# boardV3.net
KiCad netlist of a schematic drawn in EAGLE
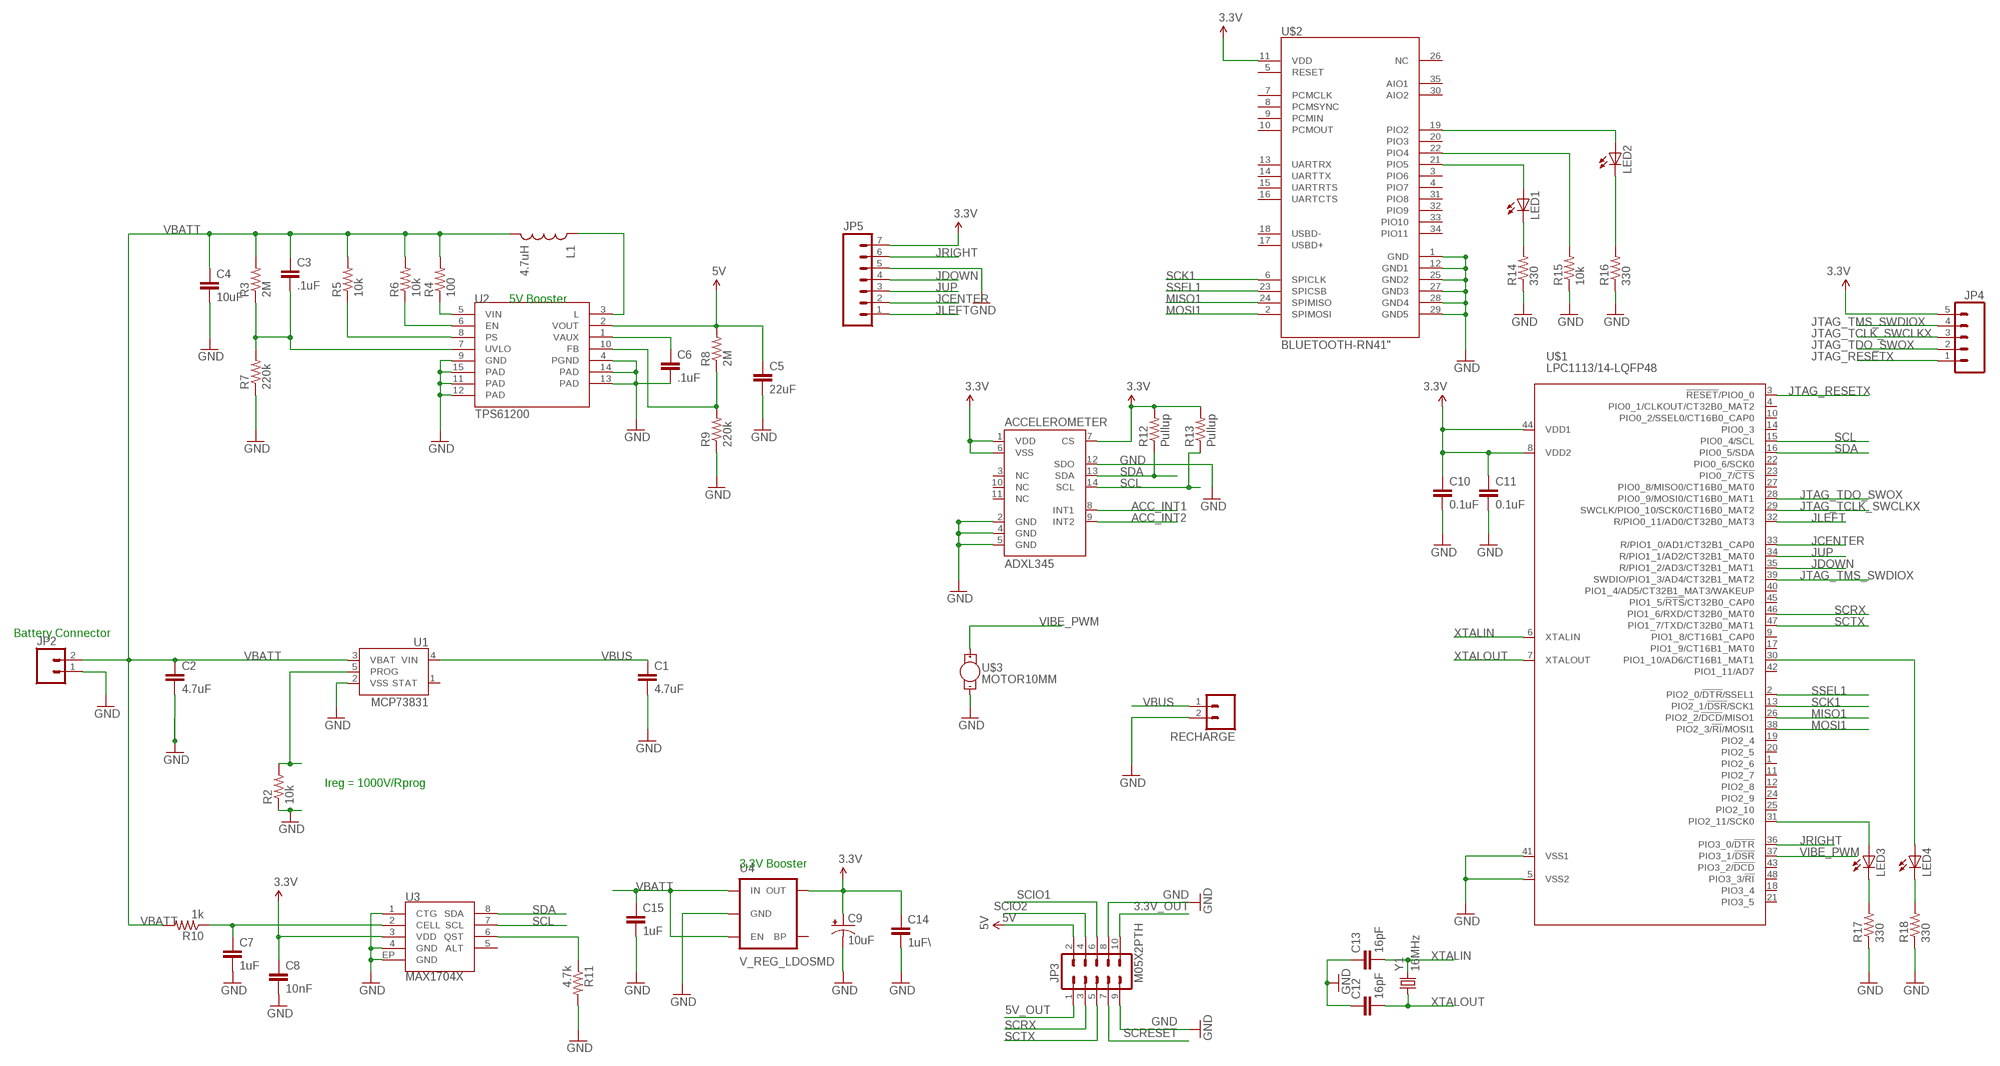
[diagram p0: schematic, sheet 1, part 1 of 2]
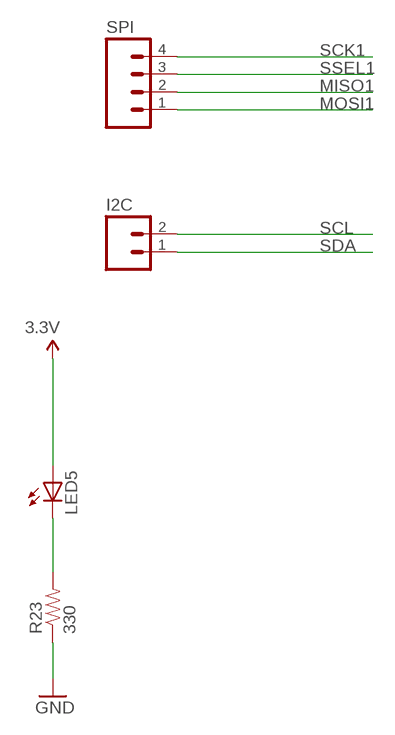
[diagram p1: schematic, sheet 1, part 2 of 2]
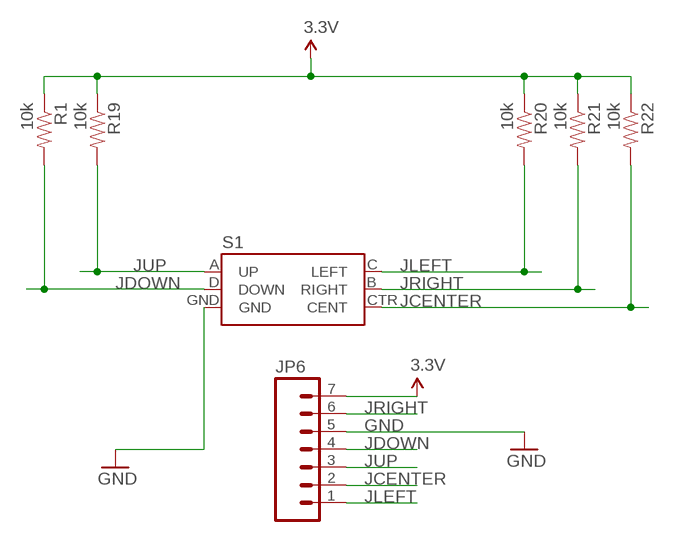
[diagram p2: schematic, sheet 2]

(export (version "E")
  (design (tool "Eeschema 10.0.6"))
  (components
    (comp (ref "ACCELEROMETER")
      (value "ADXL345")
      (footprint "eagle-import:LGA14")
      (libsource (lib "eagle-import") (part "ADXL345"))
    )
    (comp (ref "C1")
      (value "4.7uF")
      (footprint "eagle-import:0603-CAP")
      (libsource (lib "eagle-import") (part "CAP0603-CAP"))
    )
    (comp (ref "C2")
      (value "4.7uF")
      (footprint "eagle-import:0603-CAP")
      (libsource (lib "eagle-import") (part "CAP0603-CAP"))
    )
    (comp (ref "C3")
      (value ".1uF")
      (footprint "eagle-import:0603-CAP")
      (libsource (lib "eagle-import") (part "CAP0603-CAP"))
    )
    (comp (ref "C4")
      (value "10uF")
      (footprint "eagle-import:0603-CAP")
      (libsource (lib "eagle-import") (part "CAP0603-CAP"))
    )
    (comp (ref "C5")
      (value "22uF")
      (footprint "eagle-import:0603-CAP")
      (libsource (lib "eagle-import") (part "CAP0603-CAP"))
    )
    (comp (ref "C6")
      (value ".1uF")
      (footprint "eagle-import:0603-CAP")
      (libsource (lib "eagle-import") (part "CAP0603-CAP"))
    )
    (comp (ref "C7")
      (value "1uF")
      (footprint "eagle-import:0603-CAP")
      (libsource (lib "eagle-import") (part "CAP0603-CAP"))
    )
    (comp (ref "C8")
      (value "10nF")
      (footprint "eagle-import:0603-CAP")
      (libsource (lib "eagle-import") (part "CAP0603-CAP"))
    )
    (comp (ref "C9")
      (value "10uF")
      (footprint "eagle-import:EIA3216")
      (libsource (lib "eagle-import") (part "10UF-TANT"))
    )
    (comp (ref "C10")
      (value "0.1uF")
      (footprint "eagle-import:0603-CAP")
      (libsource (lib "eagle-import") (part "CAP0603-CAP"))
    )
    (comp (ref "C11")
      (value "0.1uF")
      (footprint "eagle-import:0603-CAP")
      (libsource (lib "eagle-import") (part "CAP0603-CAP"))
    )
    (comp (ref "C12")
      (value "16pF")
      (footprint "eagle-import:0603-CAP")
      (libsource (lib "eagle-import") (part "CAP0603-CAP"))
    )
    (comp (ref "C13")
      (value "16pF")
      (footprint "eagle-import:0603-CAP")
      (libsource (lib "eagle-import") (part "CAP0603-CAP"))
    )
    (comp (ref "C14")
      (value "1uF\\")
      (footprint "eagle-import:0603-CAP")
      (libsource (lib "eagle-import") (part "CAP0603-CAP"))
    )
    (comp (ref "C15")
      (value "1uF")
      (footprint "eagle-import:0603-CAP")
      (libsource (lib "eagle-import") (part "CAP0603-CAP"))
    )
    (comp (ref "I2C")
      (value "M02POLAR")
      (footprint "eagle-import:MOLEX-1X2")
      (libsource (lib "eagle-import") (part "M02POLAR"))
    )
    (comp (ref "JP2")
      (value "M02PTH")
      (footprint "eagle-import:1X02")
      (libsource (lib "eagle-import") (part "M02PTH"))
    )
    (comp (ref "JP3")
      (value "M05X2PTH")
      (footprint "eagle-import:AVR_ICSP")
      (libsource (lib "eagle-import") (part "M05X2PTH"))
    )
    (comp (ref "JP4")
      (value "M05PTH")
      (footprint "eagle-import:1X05")
      (libsource (lib "eagle-import") (part "M05PTH"))
    )
    (comp (ref "JP5")
      (value "M07")
      (footprint "eagle-import:1X07")
      (libsource (lib "eagle-import") (part "M07"))
    )
    (comp (ref "L1")
      (value "4.7uH")
      (footprint "eagle-import:CDRH2D09")
      (libsource (lib "eagle-import") (part "INDUCTOR."))
    )
    (comp (ref "LED1")
      (value "LED0603")
      (footprint "eagle-import:LED-0603")
      (libsource (lib "eagle-import") (part "LED0603"))
    )
    (comp (ref "LED2")
      (value "LED0603")
      (footprint "eagle-import:LED-0603")
      (libsource (lib "eagle-import") (part "LED0603"))
    )
    (comp (ref "LED3")
      (value "LED0603")
      (footprint "eagle-import:LED-0603")
      (libsource (lib "eagle-import") (part "LED0603"))
    )
    (comp (ref "LED4")
      (value "LED0603")
      (footprint "eagle-import:LED-0603")
      (libsource (lib "eagle-import") (part "LED0603"))
    )
    (comp (ref "LED5")
      (value "LED0603")
      (footprint "eagle-import:LED-0603")
      (libsource (lib "eagle-import") (part "LED0603"))
    )
    (comp (ref "R2")
      (value "10k")
      (footprint "eagle-import:0603-RES")
      (libsource (lib "eagle-import") (part "RESISTOR0603-RES"))
    )
    (comp (ref "R3")
      (value "2M")
      (footprint "eagle-import:0603-RES")
      (libsource (lib "eagle-import") (part "RESISTOR0603-RES"))
    )
    (comp (ref "R4")
      (value "100")
      (footprint "eagle-import:0603-RES")
      (libsource (lib "eagle-import") (part "RESISTOR0603-RES"))
    )
    (comp (ref "R5")
      (value "10k")
      (footprint "eagle-import:0603-RES")
      (libsource (lib "eagle-import") (part "RESISTOR0603-RES"))
    )
    (comp (ref "R6")
      (value "10k")
      (footprint "eagle-import:0603-RES")
      (libsource (lib "eagle-import") (part "RESISTOR0603-RES"))
    )
    (comp (ref "R7")
      (value "220k")
      (footprint "eagle-import:0603-RES")
      (libsource (lib "eagle-import") (part "RESISTOR0603-RES"))
    )
    (comp (ref "R8")
      (value "2M")
      (footprint "eagle-import:0603-RES")
      (libsource (lib "eagle-import") (part "SparkFun-Resistors_RESISTOR0603-RES"))
    )
    (comp (ref "R9")
      (value "220k")
      (footprint "eagle-import:0603-RES")
      (libsource (lib "eagle-import") (part "SparkFun-Resistors_RESISTOR0603-RES"))
    )
    (comp (ref "R10")
      (value "1k")
      (footprint "eagle-import:0603-RES")
      (libsource (lib "eagle-import") (part "RESISTOR0603-RES"))
    )
    (comp (ref "R11")
      (value "4.7k")
      (footprint "eagle-import:0603-RES")
      (libsource (lib "eagle-import") (part "RESISTOR0603-RES"))
    )
    (comp (ref "R12")
      (value "Pullup")
      (footprint "eagle-import:0603-RES")
      (libsource (lib "eagle-import") (part "SparkFun-Resistors_RESISTOR0603-RES"))
    )
    (comp (ref "R13")
      (value "Pullup")
      (footprint "eagle-import:0603-RES")
      (libsource (lib "eagle-import") (part "SparkFun-Resistors_RESISTOR0603-RES"))
    )
    (comp (ref "R14")
      (value "330")
      (footprint "eagle-import:0603-RES")
      (libsource (lib "eagle-import") (part "RESISTOR0603-RES"))
    )
    (comp (ref "R15")
      (value "10k")
      (footprint "eagle-import:0603-RES")
      (libsource (lib "eagle-import") (part "RESISTOR0603-RES"))
    )
    (comp (ref "R16")
      (value "330")
      (footprint "eagle-import:0603-RES")
      (libsource (lib "eagle-import") (part "RESISTOR0603-RES"))
    )
    (comp (ref "R17")
      (value "330")
      (footprint "eagle-import:0603-RES")
      (libsource (lib "eagle-import") (part "RESISTOR0603-RES"))
    )
    (comp (ref "R18")
      (value "330")
      (footprint "eagle-import:0603-RES")
      (libsource (lib "eagle-import") (part "RESISTOR0603-RES"))
    )
    (comp (ref "R23")
      (value "330")
      (footprint "eagle-import:0603-RES")
      (libsource (lib "eagle-import") (part "RESISTOR0603-RES"))
    )
    (comp (ref "RECHARGE")
      (value "M02POLAR")
      (footprint "eagle-import:MOLEX-1X2")
      (libsource (lib "eagle-import") (part "M02POLAR"))
    )
    (comp (ref "SPI")
      (value "M04POLAR")
      (footprint "eagle-import:MOLEX-1X4")
      (libsource (lib "eagle-import") (part "M04POLAR"))
    )
    (comp (ref "U$1")
      (value "LPC1113/14-LQFP48")
      (footprint "eagle-import:LQFP48")
      (libsource (lib "eagle-import") (part "LPC1113/14-LQFP48"))
    )
    (comp (ref "U$2")
      (value "BLUETOOTH-RN41\"")
      (footprint "eagle-import:RN41")
      (libsource (lib "eagle-import") (part "BLUETOOTH-RN41{dblquote}"))
    )
    (comp (ref "U$3")
      (value "MOTOR10MM")
      (footprint "eagle-import:VIBE-MOTOR-10MM")
      (libsource (lib "eagle-import") (part "MOTOR10MM"))
    )
    (comp (ref "U1")
      (value "MCP73831")
      (footprint "eagle-import:SOT23-5")
      (libsource (lib "eagle-import") (part "MCP73831"))
    )
    (comp (ref "U2")
      (value "TPS61200")
      (footprint "eagle-import:QFN-10_PAD")
      (libsource (lib "eagle-import") (part "TPS61200"))
    )
    (comp (ref "U3")
      (value "MAX1704X")
      (footprint "eagle-import:TDFN-8")
      (libsource (lib "eagle-import") (part "MAX1704X"))
    )
    (comp (ref "U4")
      (value "V_REG_LDOSMD")
      (footprint "eagle-import:SOT23-5")
      (libsource (lib "eagle-import") (part "V_REG_LDOSMD"))
    )
    (comp (ref "Y1")
      (value "16MHz")
      (footprint "eagle-import:CRYSTAL-SMD-5X3")
      (libsource (lib "eagle-import") (part "CRYSTAL5X3"))
    )
    (comp (ref "JP6")
      (value "M07")
      (footprint "eagle-import:1X07")
      (libsource (lib "eagle-import") (part "M07"))
    )
    (comp (ref "R1")
      (value "10k")
      (footprint "eagle-import:0603-RES")
      (libsource (lib "eagle-import") (part "SparkFun-Resistors_RESISTOR0603-RES"))
    )
    (comp (ref "R19")
      (value "10k")
      (footprint "eagle-import:0603-RES")
      (libsource (lib "eagle-import") (part "SparkFun-Resistors_RESISTOR0603-RES"))
    )
    (comp (ref "R20")
      (value "10k")
      (footprint "eagle-import:0603-RES")
      (libsource (lib "eagle-import") (part "SparkFun-Resistors_RESISTOR0603-RES"))
    )
    (comp (ref "R21")
      (value "10k")
      (footprint "eagle-import:0603-RES")
      (libsource (lib "eagle-import") (part "SparkFun-Resistors_RESISTOR0603-RES"))
    )
    (comp (ref "R22")
      (value "10k")
      (footprint "eagle-import:0603-RES")
      (libsource (lib "eagle-import") (part "SparkFun-Resistors_RESISTOR0603-RES"))
    )
    (comp (ref "S1")
      (value "JOYSTICK_MINI")
      (footprint "eagle-import:JOYSTICK_MINI")
      (libsource (lib "eagle-import") (part "JOYSTICK_MINI"))
    )
  )
  (nets
    (net (code "1") (name "3.3V") (class "Default")
      (node (ref "ACCELEROMETER") (pin "1") (pinfunction "VDD_1") (pintype "bidirectional"))
      (node (ref "ACCELEROMETER") (pin "6") (pinfunction "VSS_6") (pintype "bidirectional"))
      (node (ref "ACCELEROMETER") (pin "7") (pinfunction "CS_7") (pintype "bidirectional"))
      (node (ref "C10") (pin "1") (pinfunction "1_1") (pintype "passive"))
      (node (ref "C11") (pin "1") (pinfunction "1_1") (pintype "passive"))
      (node (ref "C14") (pin "1") (pinfunction "1_1") (pintype "passive"))
      (node (ref "C8") (pin "1") (pinfunction "1_1") (pintype "passive"))
      (node (ref "C9") (pin "A") (pinfunction "+_A") (pintype "passive"))
      (node (ref "JP4") (pin "5") (pinfunction "5_5") (pintype "passive"))
      (node (ref "JP5") (pin "7") (pinfunction "7_7") (pintype "passive"))
      (node (ref "JP6") (pin "7") (pinfunction "7_7") (pintype "passive"))
      (node (ref "LED5") (pin "A") (pinfunction "A_A") (pintype "passive"))
      (node (ref "R1") (pin "1") (pinfunction "1_1") (pintype "passive"))
      (node (ref "R12") (pin "2") (pinfunction "2_2") (pintype "passive"))
      (node (ref "R13") (pin "2") (pinfunction "2_2") (pintype "passive"))
      (node (ref "R19") (pin "1") (pinfunction "1_1") (pintype "passive"))
      (node (ref "R20") (pin "1") (pinfunction "1_1") (pintype "passive"))
      (node (ref "R21") (pin "1") (pinfunction "1_1") (pintype "passive"))
      (node (ref "R22") (pin "1") (pinfunction "1_1") (pintype "passive"))
      (node (ref "U$1") (pin "44") (pinfunction "VDD1_44") (pintype "power_in"))
      (node (ref "U$1") (pin "8") (pinfunction "VDD2_8") (pintype "power_in"))
      (node (ref "U$2") (pin "11") (pinfunction "VDD_11") (pintype "bidirectional"))
      (node (ref "U3") (pin "3") (pinfunction "VDD_3") (pintype "bidirectional"))
      (node (ref "U4") (pin "5") (pinfunction "OUT_5") (pintype "passive"))
    )
    (net (code "2") (name "3.3V_OUT") (class "Default")
      (node (ref "JP3") (pin "10") (pinfunction "10_10") (pintype "passive"))
    )
    (net (code "3") (name "5V") (class "Default")
      (node (ref "C5") (pin "1") (pinfunction "1_1") (pintype "passive"))
      (node (ref "JP3") (pin "2") (pinfunction "2_2") (pintype "passive"))
      (node (ref "R8") (pin "2") (pinfunction "2_2") (pintype "passive"))
      (node (ref "U2") (pin "2") (pinfunction "VOUT_2") (pintype "passive"))
    )
    (net (code "4") (name "5V_OUT") (class "Default")
      (node (ref "JP3") (pin "1") (pinfunction "1_1") (pintype "passive"))
    )
    (net (code "5") (name "ACC_INT1") (class "Default")
      (node (ref "ACCELEROMETER") (pin "8") (pinfunction "INT1_8") (pintype "bidirectional"))
    )
    (net (code "6") (name "ACC_INT2") (class "Default")
      (node (ref "ACCELEROMETER") (pin "9") (pinfunction "INT2_9") (pintype "bidirectional"))
    )
    (net (code "7") (name "GND") (class "Default")
      (node (ref "ACCELEROMETER") (pin "12") (pinfunction "SDO_12") (pintype "bidirectional"))
      (node (ref "ACCELEROMETER") (pin "2") (pinfunction "GND_2") (pintype "bidirectional"))
      (node (ref "ACCELEROMETER") (pin "4") (pinfunction "GND_4") (pintype "bidirectional"))
      (node (ref "ACCELEROMETER") (pin "5") (pinfunction "GND_5") (pintype "bidirectional"))
      (node (ref "C1") (pin "2") (pinfunction "2_2") (pintype "passive"))
      (node (ref "C10") (pin "2") (pinfunction "2_2") (pintype "passive"))
      (node (ref "C11") (pin "2") (pinfunction "2_2") (pintype "passive"))
      (node (ref "C12") (pin "1") (pinfunction "1_1") (pintype "passive"))
      (node (ref "C13") (pin "1") (pinfunction "1_1") (pintype "passive"))
      (node (ref "C14") (pin "2") (pinfunction "2_2") (pintype "passive"))
      (node (ref "C15") (pin "2") (pinfunction "2_2") (pintype "passive"))
      (node (ref "C2") (pin "2") (pinfunction "2_2") (pintype "passive"))
      (node (ref "C4") (pin "2") (pinfunction "2_2") (pintype "passive"))
      (node (ref "C5") (pin "2") (pinfunction "2_2") (pintype "passive"))
      (node (ref "C6") (pin "2") (pinfunction "2_2") (pintype "passive"))
      (node (ref "C7") (pin "2") (pinfunction "2_2") (pintype "passive"))
      (node (ref "C8") (pin "2") (pinfunction "2_2") (pintype "passive"))
      (node (ref "C9") (pin "C") (pinfunction "-_C") (pintype "passive"))
      (node (ref "JP2") (pin "1") (pinfunction "1_1") (pintype "passive"))
      (node (ref "JP3") (pin "8") (pinfunction "8_8") (pintype "passive"))
      (node (ref "JP3") (pin "9") (pinfunction "9_9") (pintype "passive"))
      (node (ref "JP5") (pin "5") (pinfunction "5_5") (pintype "passive"))
      (node (ref "JP6") (pin "5") (pinfunction "5_5") (pintype "passive"))
      (node (ref "R11") (pin "2") (pinfunction "2_2") (pintype "passive"))
      (node (ref "R14") (pin "1") (pinfunction "1_1") (pintype "passive"))
      (node (ref "R15") (pin "1") (pinfunction "1_1") (pintype "passive"))
      (node (ref "R16") (pin "1") (pinfunction "1_1") (pintype "passive"))
      (node (ref "R17") (pin "1") (pinfunction "1_1") (pintype "passive"))
      (node (ref "R18") (pin "1") (pinfunction "1_1") (pintype "passive"))
      (node (ref "R2") (pin "1") (pinfunction "1_1") (pintype "passive"))
      (node (ref "R23") (pin "1") (pinfunction "1_1") (pintype "passive"))
      (node (ref "R7") (pin "1") (pinfunction "1_1") (pintype "passive"))
      (node (ref "R9") (pin "1") (pinfunction "1_1") (pintype "passive"))
      (node (ref "RECHARGE") (pin "2") (pinfunction "2_2") (pintype "passive"))
      (node (ref "S1") (pin "GND") (pinfunction "GND_GND") (pintype "bidirectional"))
      (node (ref "U$1") (pin "41") (pinfunction "VSS1_41") (pintype "power_in"))
      (node (ref "U$1") (pin "5") (pinfunction "VSS2_5") (pintype "power_in"))
      (node (ref "U$2") (pin "1") (pinfunction "GND_1") (pintype "bidirectional"))
      (node (ref "U$2") (pin "12") (pinfunction "GND1_12") (pintype "bidirectional"))
      (node (ref "U$2") (pin "25") (pinfunction "GND2_25") (pintype "bidirectional"))
      (node (ref "U$2") (pin "27") (pinfunction "GND3_27") (pintype "bidirectional"))
      (node (ref "U$2") (pin "28") (pinfunction "GND4_28") (pintype "bidirectional"))
      (node (ref "U$2") (pin "29") (pinfunction "GND5_29") (pintype "bidirectional"))
      (node (ref "U$3") (pin "-") (pinfunction "-_-") (pintype "bidirectional"))
      (node (ref "U1") (pin "2") (pinfunction "VSS_2") (pintype "power_in"))
      (node (ref "U2") (pin "11") (pinfunction "PAD_11") (pintype "power_in"))
      (node (ref "U2") (pin "12") (pinfunction "PAD_12") (pintype "power_in"))
      (node (ref "U2") (pin "13") (pinfunction "PAD_13") (pintype "power_in"))
      (node (ref "U2") (pin "14") (pinfunction "PAD_14") (pintype "power_in"))
      (node (ref "U2") (pin "15") (pinfunction "PAD_15") (pintype "power_in"))
      (node (ref "U2") (pin "4") (pinfunction "PGND_4") (pintype "power_in"))
      (node (ref "U2") (pin "9") (pinfunction "GND_9") (pintype "power_in"))
      (node (ref "U3") (pin "1") (pinfunction "CTG_1") (pintype "bidirectional"))
      (node (ref "U3") (pin "4") (pinfunction "GND_4") (pintype "bidirectional"))
      (node (ref "U3") (pin "EP") (pinfunction "GND_EP") (pintype "bidirectional"))
      (node (ref "U4") (pin "2") (pinfunction "GND_2") (pintype "input"))
    )
    (net (code "8") (name "JCENTER") (class "Default")
      (node (ref "JP5") (pin "2") (pinfunction "2_2") (pintype "passive"))
      (node (ref "JP6") (pin "2") (pinfunction "2_2") (pintype "passive"))
      (node (ref "R22") (pin "2") (pinfunction "2_2") (pintype "passive"))
      (node (ref "S1") (pin "CTR") (pinfunction "CENT_CTR") (pintype "bidirectional"))
      (node (ref "U$1") (pin "33") (pinfunction "R/PIO1_0/AD1/CT32B1_CAP0_33") (pintype "bidirectional"))
    )
    (net (code "9") (name "JDOWN") (class "Default")
      (node (ref "JP5") (pin "4") (pinfunction "4_4") (pintype "passive"))
      (node (ref "JP6") (pin "4") (pinfunction "4_4") (pintype "passive"))
      (node (ref "R1") (pin "2") (pinfunction "2_2") (pintype "passive"))
      (node (ref "S1") (pin "D") (pinfunction "DOWN_D") (pintype "bidirectional"))
      (node (ref "U$1") (pin "35") (pinfunction "R/PIO1_2/AD3/CT32B1_MAT1_35") (pintype "bidirectional"))
    )
    (net (code "10") (name "JLEFT") (class "Default")
      (node (ref "JP5") (pin "1") (pinfunction "1_1") (pintype "passive"))
      (node (ref "JP6") (pin "1") (pinfunction "1_1") (pintype "passive"))
      (node (ref "R20") (pin "2") (pinfunction "2_2") (pintype "passive"))
      (node (ref "S1") (pin "C") (pinfunction "LEFT_C") (pintype "bidirectional"))
      (node (ref "U$1") (pin "32") (pinfunction "R/PIO0_11/AD0/CT32B0_MAT3_32") (pintype "bidirectional"))
    )
    (net (code "11") (name "JRIGHT") (class "Default")
      (node (ref "JP5") (pin "6") (pinfunction "6_6") (pintype "passive"))
      (node (ref "JP6") (pin "6") (pinfunction "6_6") (pintype "passive"))
      (node (ref "R21") (pin "2") (pinfunction "2_2") (pintype "passive"))
      (node (ref "S1") (pin "B") (pinfunction "RIGHT_B") (pintype "bidirectional"))
      (node (ref "U$1") (pin "36") (pinfunction "PIO3_0/~{DTR}_36") (pintype "bidirectional"))
    )
    (net (code "12") (name "JTAG_RESETX") (class "Default")
      (node (ref "JP4") (pin "1") (pinfunction "1_1") (pintype "passive"))
      (node (ref "U$1") (pin "3") (pinfunction "~{RESET}/PIO0_0_3") (pintype "bidirectional"))
    )
    (net (code "13") (name "JTAG_TCLK_SWCLKX") (class "Default")
      (node (ref "JP4") (pin "3") (pinfunction "3_3") (pintype "passive"))
      (node (ref "U$1") (pin "29") (pinfunction "SWCLK/PIO0_10/SCK0/CT16B0_MAT2_29") (pintype "bidirectional"))
    )
    (net (code "14") (name "JTAG_TDO_SWOX") (class "Default")
      (node (ref "JP4") (pin "2") (pinfunction "2_2") (pintype "passive"))
      (node (ref "U$1") (pin "28") (pinfunction "PIO0_9/MOSI0/CT16B0_MAT1_28") (pintype "bidirectional"))
    )
    (net (code "15") (name "JTAG_TMS_SWDIOX") (class "Default")
      (node (ref "JP4") (pin "4") (pinfunction "4_4") (pintype "passive"))
      (node (ref "U$1") (pin "39") (pinfunction "SWDIO/PIO1_3/AD4/CT32B1_MAT2_39") (pintype "bidirectional"))
    )
    (net (code "16") (name "JUP") (class "Default")
      (node (ref "JP5") (pin "3") (pinfunction "3_3") (pintype "passive"))
      (node (ref "JP6") (pin "3") (pinfunction "3_3") (pintype "passive"))
      (node (ref "R19") (pin "2") (pinfunction "2_2") (pintype "passive"))
      (node (ref "S1") (pin "A") (pinfunction "UP_A") (pintype "bidirectional"))
      (node (ref "U$1") (pin "34") (pinfunction "R/PIO1_1/AD2/CT32B1_MAT0_34") (pintype "bidirectional"))
    )
    (net (code "17") (name "MISO1") (class "Default")
      (node (ref "SPI") (pin "2") (pinfunction "2_2") (pintype "passive"))
      (node (ref "U$1") (pin "26") (pinfunction "PIO2_2/~{DCD}/MISO1_26") (pintype "bidirectional"))
      (node (ref "U$2") (pin "24") (pinfunction "SPIMISO_24") (pintype "bidirectional"))
    )
    (net (code "18") (name "MOSI1") (class "Default")
      (node (ref "SPI") (pin "1") (pinfunction "1_1") (pintype "passive"))
      (node (ref "U$1") (pin "38") (pinfunction "PIO2_3/~{RI}/MOSI1_38") (pintype "bidirectional"))
      (node (ref "U$2") (pin "2") (pinfunction "SPIMOSI_2") (pintype "bidirectional"))
    )
    (net (code "19") (name "Net-(L1-1)") (class "Default")
      (node (ref "L1") (pin "P$1") (pinfunction "1_P$1") (pintype "passive"))
      (node (ref "U2") (pin "3") (pinfunction "L_3") (pintype "passive"))
    )
    (net (code "20") (name "Net-(LED1-PadC)") (class "Default")
      (node (ref "LED1") (pin "C") (pinfunction "C_C") (pintype "passive"))
      (node (ref "R14") (pin "2") (pinfunction "2_2") (pintype "passive"))
    )
    (net (code "21") (name "Net-(LED2-PadC)") (class "Default")
      (node (ref "LED2") (pin "C") (pinfunction "C_C") (pintype "passive"))
      (node (ref "R16") (pin "2") (pinfunction "2_2") (pintype "passive"))
    )
    (net (code "22") (name "Net-(LED3-PadC)") (class "Default")
      (node (ref "LED3") (pin "C") (pinfunction "C_C") (pintype "passive"))
      (node (ref "R17") (pin "2") (pinfunction "2_2") (pintype "passive"))
    )
    (net (code "23") (name "Net-(LED4-PadC)") (class "Default")
      (node (ref "LED4") (pin "C") (pinfunction "C_C") (pintype "passive"))
      (node (ref "R18") (pin "2") (pinfunction "2_2") (pintype "passive"))
    )
    (net (code "24") (name "Net-(LED5-PadC)") (class "Default")
      (node (ref "LED5") (pin "C") (pinfunction "C_C") (pintype "passive"))
      (node (ref "R23") (pin "2") (pinfunction "2_2") (pintype "passive"))
    )
    (net (code "25") (name "Net-(U$1-PIO1_10{slash}AD6{slash}CT16B1_MAT1)") (class "Default")
      (node (ref "LED4") (pin "A") (pinfunction "A_A") (pintype "passive"))
      (node (ref "U$1") (pin "30") (pinfunction "PIO1_10/AD6/CT16B1_MAT1_30") (pintype "bidirectional"))
    )
    (net (code "26") (name "Net-(U$1-PIO2_11{slash}SCK0)") (class "Default")
      (node (ref "LED3") (pin "A") (pinfunction "A_A") (pintype "passive"))
      (node (ref "U$1") (pin "31") (pinfunction "PIO2_11/SCK0_31") (pintype "bidirectional"))
    )
    (net (code "27") (name "Net-(U$2-PIO2)") (class "Default")
      (node (ref "LED2") (pin "A") (pinfunction "A_A") (pintype "passive"))
      (node (ref "U$2") (pin "19") (pinfunction "PIO2_19") (pintype "bidirectional"))
    )
    (net (code "28") (name "Net-(U$2-PIO4)") (class "Default")
      (node (ref "R15") (pin "2") (pinfunction "2_2") (pintype "passive"))
      (node (ref "U$2") (pin "22") (pinfunction "PIO4_22") (pintype "bidirectional"))
    )
    (net (code "29") (name "Net-(U$2-PIO5)") (class "Default")
      (node (ref "LED1") (pin "A") (pinfunction "A_A") (pintype "passive"))
      (node (ref "U$2") (pin "21") (pinfunction "PIO5_21") (pintype "bidirectional"))
    )
    (net (code "30") (name "Net-(U1-PROG)") (class "Default")
      (node (ref "R2") (pin "2") (pinfunction "2_2") (pintype "passive"))
      (node (ref "U1") (pin "5") (pinfunction "PROG_5") (pintype "input"))
    )
    (net (code "31") (name "Net-(U2-EN)") (class "Default")
      (node (ref "R6") (pin "1") (pinfunction "1_1") (pintype "passive"))
      (node (ref "U2") (pin "6") (pinfunction "EN_6") (pintype "input"))
    )
    (net (code "32") (name "Net-(U2-FB)") (class "Default")
      (node (ref "R8") (pin "1") (pinfunction "1_1") (pintype "passive"))
      (node (ref "R9") (pin "2") (pinfunction "2_2") (pintype "passive"))
      (node (ref "U2") (pin "10") (pinfunction "FB_10") (pintype "passive"))
    )
    (net (code "33") (name "Net-(U2-PS)") (class "Default")
      (node (ref "R5") (pin "1") (pinfunction "1_1") (pintype "passive"))
      (node (ref "U2") (pin "8") (pinfunction "PS_8") (pintype "input"))
    )
    (net (code "34") (name "Net-(U2-UVLO)") (class "Default")
      (node (ref "C3") (pin "2") (pinfunction "2_2") (pintype "passive"))
      (node (ref "R3") (pin "1") (pinfunction "1_1") (pintype "passive"))
      (node (ref "R7") (pin "2") (pinfunction "2_2") (pintype "passive"))
      (node (ref "U2") (pin "7") (pinfunction "UVLO_7") (pintype "passive"))
    )
    (net (code "35") (name "Net-(U2-VAUX)") (class "Default")
      (node (ref "C6") (pin "1") (pinfunction "1_1") (pintype "passive"))
      (node (ref "U2") (pin "1") (pinfunction "VAUX_1") (pintype "passive"))
    )
    (net (code "36") (name "Net-(U2-VIN)") (class "Default")
      (node (ref "R4") (pin "1") (pinfunction "1_1") (pintype "passive"))
      (node (ref "U2") (pin "5") (pinfunction "VIN_5") (pintype "power_in"))
    )
    (net (code "37") (name "Net-(U3-CELL)") (class "Default")
      (node (ref "C7") (pin "1") (pinfunction "1_1") (pintype "passive"))
      (node (ref "R10") (pin "1") (pinfunction "1_1") (pintype "passive"))
      (node (ref "U3") (pin "2") (pinfunction "CELL_2") (pintype "bidirectional"))
    )
    (net (code "38") (name "Net-(U3-QST)") (class "Default")
      (node (ref "R11") (pin "1") (pinfunction "1_1") (pintype "passive"))
      (node (ref "U3") (pin "6") (pinfunction "QST_6") (pintype "bidirectional"))
    )
    (net (code "39") (name "SCIO1") (class "Default")
      (node (ref "JP3") (pin "6") (pinfunction "6_6") (pintype "passive"))
    )
    (net (code "40") (name "SCIO2") (class "Default")
      (node (ref "JP3") (pin "4") (pinfunction "4_4") (pintype "passive"))
    )
    (net (code "41") (name "SCK1") (class "Default")
      (node (ref "SPI") (pin "4") (pinfunction "4_4") (pintype "passive"))
      (node (ref "U$1") (pin "13") (pinfunction "PIO2_1/~{DSR}/SCK1_13") (pintype "bidirectional"))
      (node (ref "U$2") (pin "6") (pinfunction "SPICLK_6") (pintype "bidirectional"))
    )
    (net (code "42") (name "SCL") (class "Default")
      (node (ref "ACCELEROMETER") (pin "14") (pinfunction "SCL_14") (pintype "bidirectional"))
      (node (ref "I2C") (pin "2") (pinfunction "2_2") (pintype "passive"))
      (node (ref "R13") (pin "1") (pinfunction "1_1") (pintype "passive"))
      (node (ref "U$1") (pin "15") (pinfunction "PIO0_4/SCL_15") (pintype "bidirectional"))
      (node (ref "U3") (pin "7") (pinfunction "SCL_7") (pintype "bidirectional"))
    )
    (net (code "43") (name "SCRESET") (class "Default")
      (node (ref "JP3") (pin "7") (pinfunction "7_7") (pintype "passive"))
    )
    (net (code "44") (name "SCRX") (class "Default")
      (node (ref "JP3") (pin "3") (pinfunction "3_3") (pintype "passive"))
      (node (ref "U$1") (pin "46") (pinfunction "PIO1_6/RXD/CT32B0_MAT0_46") (pintype "bidirectional"))
    )
    (net (code "45") (name "SCTX") (class "Default")
      (node (ref "JP3") (pin "5") (pinfunction "5_5") (pintype "passive"))
      (node (ref "U$1") (pin "47") (pinfunction "PIO1_7/TXD/CT32B0_MAT1_47") (pintype "bidirectional"))
    )
    (net (code "46") (name "SDA") (class "Default")
      (node (ref "ACCELEROMETER") (pin "13") (pinfunction "SDA_13") (pintype "bidirectional"))
      (node (ref "I2C") (pin "1") (pinfunction "1_1") (pintype "passive"))
      (node (ref "R12") (pin "1") (pinfunction "1_1") (pintype "passive"))
      (node (ref "U$1") (pin "16") (pinfunction "PIO0_5/SDA_16") (pintype "bidirectional"))
      (node (ref "U3") (pin "8") (pinfunction "SDA_8") (pintype "bidirectional"))
    )
    (net (code "47") (name "SSEL1") (class "Default")
      (node (ref "SPI") (pin "3") (pinfunction "3_3") (pintype "passive"))
      (node (ref "U$1") (pin "2") (pinfunction "PIO2_0/~{DTR}/SSEL1_2") (pintype "bidirectional"))
      (node (ref "U$2") (pin "23") (pinfunction "SPICSB_23") (pintype "bidirectional"))
    )
    (net (code "48") (name "VBATT") (class "Default")
      (node (ref "C15") (pin "1") (pinfunction "1_1") (pintype "passive"))
      (node (ref "C2") (pin "1") (pinfunction "1_1") (pintype "passive"))
      (node (ref "C3") (pin "1") (pinfunction "1_1") (pintype "passive"))
      (node (ref "C4") (pin "1") (pinfunction "1_1") (pintype "passive"))
      (node (ref "JP2") (pin "2") (pinfunction "2_2") (pintype "passive"))
      (node (ref "L1") (pin "P$2") (pinfunction "2_P$2") (pintype "passive"))
      (node (ref "R10") (pin "2") (pinfunction "2_2") (pintype "passive"))
      (node (ref "R3") (pin "2") (pinfunction "2_2") (pintype "passive"))
      (node (ref "R4") (pin "2") (pinfunction "2_2") (pintype "passive"))
      (node (ref "R5") (pin "2") (pinfunction "2_2") (pintype "passive"))
      (node (ref "R6") (pin "2") (pinfunction "2_2") (pintype "passive"))
      (node (ref "U1") (pin "3") (pinfunction "VBAT_3") (pintype "power_in"))
      (node (ref "U4") (pin "1") (pinfunction "IN_1") (pintype "input"))
      (node (ref "U4") (pin "3") (pinfunction "EN_3") (pintype "input"))
    )
    (net (code "49") (name "VBUS") (class "Default")
      (node (ref "C1") (pin "1") (pinfunction "1_1") (pintype "passive"))
      (node (ref "RECHARGE") (pin "1") (pinfunction "1_1") (pintype "passive"))
      (node (ref "U1") (pin "4") (pinfunction "VIN_4") (pintype "power_in"))
    )
    (net (code "50") (name "VIBE_PWM") (class "Default")
      (node (ref "U$1") (pin "37") (pinfunction "PIO3_1/~{DSR}_37") (pintype "bidirectional"))
      (node (ref "U$3") (pin "+") (pinfunction "+_+") (pintype "bidirectional"))
    )
    (net (code "51") (name "XTALIN") (class "Default")
      (node (ref "C13") (pin "2") (pinfunction "2_2") (pintype "passive"))
      (node (ref "U$1") (pin "6") (pinfunction "XTALIN_6") (pintype "passive"))
      (node (ref "Y1") (pin "3") (pinfunction "2_3") (pintype "passive"))
    )
    (net (code "52") (name "XTALOUT") (class "Default")
      (node (ref "C12") (pin "2") (pinfunction "2_2") (pintype "passive"))
      (node (ref "U$1") (pin "7") (pinfunction "XTALOUT_7") (pintype "passive"))
      (node (ref "Y1") (pin "1") (pinfunction "1_1") (pintype "passive"))
    )
    (net (code "53") (name "unconnected-(ACCELEROMETER-NC-Pad3)") (class "Default")
      (node (ref "ACCELEROMETER") (pin "3") (pinfunction "NC_3") (pintype "bidirectional"))
    )
    (net (code "54") (name "unconnected-(ACCELEROMETER-NC-Pad10)") (class "Default")
      (node (ref "ACCELEROMETER") (pin "10") (pinfunction "NC_10") (pintype "bidirectional"))
    )
    (net (code "55") (name "unconnected-(ACCELEROMETER-NC-Pad11)") (class "Default")
      (node (ref "ACCELEROMETER") (pin "11") (pinfunction "NC_11") (pintype "bidirectional"))
    )
    (net (code "56") (name "unconnected-(U$1-PIO0_1{slash}CLKOUT{slash}CT32B0_MAT2-Pad4)") (class "Default")
      (node (ref "U$1") (pin "4") (pinfunction "PIO0_1/CLKOUT/CT32B0_MAT2_4") (pintype "bidirectional"))
    )
    (net (code "57") (name "unconnected-(U$1-PIO0_2{slash}SSEL0{slash}CT16B0_CAP0-Pad10)") (class "Default")
      (node (ref "U$1") (pin "10") (pinfunction "PIO0_2/SSEL0/CT16B0_CAP0_10") (pintype "bidirectional"))
    )
    (net (code "58") (name "unconnected-(U$1-PIO0_3-Pad14)") (class "Default")
      (node (ref "U$1") (pin "14") (pinfunction "PIO0_3_14") (pintype "bidirectional"))
    )
    (net (code "59") (name "unconnected-(U$1-PIO0_6{slash}SCK0-Pad22)") (class "Default")
      (node (ref "U$1") (pin "22") (pinfunction "PIO0_6/SCK0_22") (pintype "bidirectional"))
    )
    (net (code "60") (name "unconnected-(U$1-PIO0_7{slash}~{CTS}-Pad23)") (class "Default")
      (node (ref "U$1") (pin "23") (pinfunction "PIO0_7/~{CTS}_23") (pintype "bidirectional"))
    )
    (net (code "61") (name "unconnected-(U$1-PIO0_8{slash}MISO0{slash}CT16B0_MAT0-Pad27)") (class "Default")
      (node (ref "U$1") (pin "27") (pinfunction "PIO0_8/MISO0/CT16B0_MAT0_27") (pintype "bidirectional"))
    )
    (net (code "62") (name "unconnected-(U$1-PIO1_4{slash}AD5{slash}CT32B1_MAT3{slash}WAKEUP-Pad40)") (class "Default")
      (node (ref "U$1") (pin "40") (pinfunction "PIO1_4/AD5/CT32B1_MAT3/WAKEUP_40") (pintype "bidirectional"))
    )
    (net (code "63") (name "unconnected-(U$1-PIO1_5{slash}~{RTS}{slash}CT32B0_CAP0-Pad45)") (class "Default")
      (node (ref "U$1") (pin "45") (pinfunction "PIO1_5/~{RTS}/CT32B0_CAP0_45") (pintype "bidirectional"))
    )
    (net (code "64") (name "unconnected-(U$1-PIO1_8{slash}CT16B1_CAP0-Pad9)") (class "Default")
      (node (ref "U$1") (pin "9") (pinfunction "PIO1_8/CT16B1_CAP0_9") (pintype "bidirectional"))
    )
    (net (code "65") (name "unconnected-(U$1-PIO1_9{slash}CT16B1_MAT0-Pad17)") (class "Default")
      (node (ref "U$1") (pin "17") (pinfunction "PIO1_9/CT16B1_MAT0_17") (pintype "bidirectional"))
    )
    (net (code "66") (name "unconnected-(U$1-PIO1_11{slash}AD7-Pad42)") (class "Default")
      (node (ref "U$1") (pin "42") (pinfunction "PIO1_11/AD7_42") (pintype "bidirectional"))
    )
    (net (code "67") (name "unconnected-(U$1-PIO2_4-Pad19)") (class "Default")
      (node (ref "U$1") (pin "19") (pinfunction "PIO2_4_19") (pintype "bidirectional"))
    )
    (net (code "68") (name "unconnected-(U$1-PIO2_5-Pad20)") (class "Default")
      (node (ref "U$1") (pin "20") (pinfunction "PIO2_5_20") (pintype "bidirectional"))
    )
    (net (code "69") (name "unconnected-(U$1-PIO2_6-Pad1)") (class "Default")
      (node (ref "U$1") (pin "1") (pinfunction "PIO2_6_1") (pintype "bidirectional"))
    )
    (net (code "70") (name "unconnected-(U$1-PIO2_7-Pad11)") (class "Default")
      (node (ref "U$1") (pin "11") (pinfunction "PIO2_7_11") (pintype "bidirectional"))
    )
    (net (code "71") (name "unconnected-(U$1-PIO2_8-Pad12)") (class "Default")
      (node (ref "U$1") (pin "12") (pinfunction "PIO2_8_12") (pintype "bidirectional"))
    )
    (net (code "72") (name "unconnected-(U$1-PIO2_9-Pad24)") (class "Default")
      (node (ref "U$1") (pin "24") (pinfunction "PIO2_9_24") (pintype "bidirectional"))
    )
    (net (code "73") (name "unconnected-(U$1-PIO2_10-Pad25)") (class "Default")
      (node (ref "U$1") (pin "25") (pinfunction "PIO2_10_25") (pintype "bidirectional"))
    )
    (net (code "74") (name "unconnected-(U$1-PIO3_2{slash}~{DCD}-Pad43)") (class "Default")
      (node (ref "U$1") (pin "43") (pinfunction "PIO3_2/~{DCD}_43") (pintype "bidirectional"))
    )
    (net (code "75") (name "unconnected-(U$1-PIO3_3{slash}~{RI}-Pad48)") (class "Default")
      (node (ref "U$1") (pin "48") (pinfunction "PIO3_3/~{RI}_48") (pintype "bidirectional"))
    )
    (net (code "76") (name "unconnected-(U$1-PIO3_4-Pad18)") (class "Default")
      (node (ref "U$1") (pin "18") (pinfunction "PIO3_4_18") (pintype "bidirectional"))
    )
    (net (code "77") (name "unconnected-(U$1-PIO3_5-Pad21)") (class "Default")
      (node (ref "U$1") (pin "21") (pinfunction "PIO3_5_21") (pintype "bidirectional"))
    )
    (net (code "78") (name "unconnected-(U$2-AIO1-Pad35)") (class "Default")
      (node (ref "U$2") (pin "35") (pinfunction "AIO1_35") (pintype "bidirectional"))
    )
    (net (code "79") (name "unconnected-(U$2-AIO2-Pad30)") (class "Default")
      (node (ref "U$2") (pin "30") (pinfunction "AIO2_30") (pintype "bidirectional"))
    )
    (net (code "80") (name "unconnected-(U$2-NC-Pad26)") (class "Default")
      (node (ref "U$2") (pin "26") (pinfunction "NC_26") (pintype "bidirectional"))
    )
    (net (code "81") (name "unconnected-(U$2-PCMCLK-Pad7)") (class "Default")
      (node (ref "U$2") (pin "7") (pinfunction "PCMCLK_7") (pintype "bidirectional"))
    )
    (net (code "82") (name "unconnected-(U$2-PCMIN-Pad9)") (class "Default")
      (node (ref "U$2") (pin "9") (pinfunction "PCMIN_9") (pintype "bidirectional"))
    )
    (net (code "83") (name "unconnected-(U$2-PCMOUT-Pad10)") (class "Default")
      (node (ref "U$2") (pin "10") (pinfunction "PCMOUT_10") (pintype "bidirectional"))
    )
    (net (code "84") (name "unconnected-(U$2-PCMSYNC-Pad8)") (class "Default")
      (node (ref "U$2") (pin "8") (pinfunction "PCMSYNC_8") (pintype "bidirectional"))
    )
    (net (code "85") (name "unconnected-(U$2-PIO3-Pad20)") (class "Default")
      (node (ref "U$2") (pin "20") (pinfunction "PIO3_20") (pintype "bidirectional"))
    )
    (net (code "86") (name "unconnected-(U$2-PIO6-Pad3)") (class "Default")
      (node (ref "U$2") (pin "3") (pinfunction "PIO6_3") (pintype "bidirectional"))
    )
    (net (code "87") (name "unconnected-(U$2-PIO7-Pad4)") (class "Default")
      (node (ref "U$2") (pin "4") (pinfunction "PIO7_4") (pintype "bidirectional"))
    )
    (net (code "88") (name "unconnected-(U$2-PIO8-Pad31)") (class "Default")
      (node (ref "U$2") (pin "31") (pinfunction "PIO8_31") (pintype "bidirectional"))
    )
    (net (code "89") (name "unconnected-(U$2-PIO9-Pad32)") (class "Default")
      (node (ref "U$2") (pin "32") (pinfunction "PIO9_32") (pintype "bidirectional"))
    )
    (net (code "90") (name "unconnected-(U$2-PIO10-Pad33)") (class "Default")
      (node (ref "U$2") (pin "33") (pinfunction "PIO10_33") (pintype "bidirectional"))
    )
    (net (code "91") (name "unconnected-(U$2-PIO11-Pad34)") (class "Default")
      (node (ref "U$2") (pin "34") (pinfunction "PIO11_34") (pintype "bidirectional"))
    )
    (net (code "92") (name "unconnected-(U$2-RESET-Pad5)") (class "Default")
      (node (ref "U$2") (pin "5") (pinfunction "RESET_5") (pintype "bidirectional"))
    )
    (net (code "93") (name "unconnected-(U$2-UARTCTS-Pad16)") (class "Default")
      (node (ref "U$2") (pin "16") (pinfunction "UARTCTS_16") (pintype "bidirectional"))
    )
    (net (code "94") (name "unconnected-(U$2-UARTRTS-Pad15)") (class "Default")
      (node (ref "U$2") (pin "15") (pinfunction "UARTRTS_15") (pintype "bidirectional"))
    )
    (net (code "95") (name "unconnected-(U$2-UARTRX-Pad13)") (class "Default")
      (node (ref "U$2") (pin "13") (pinfunction "UARTRX_13") (pintype "bidirectional"))
    )
    (net (code "96") (name "unconnected-(U$2-UARTTX-Pad14)") (class "Default")
      (node (ref "U$2") (pin "14") (pinfunction "UARTTX_14") (pintype "bidirectional"))
    )
    (net (code "97") (name "unconnected-(U$2-USBD+-Pad17)") (class "Default")
      (node (ref "U$2") (pin "17") (pinfunction "USBD+_17") (pintype "bidirectional"))
    )
    (net (code "98") (name "unconnected-(U$2-USBD--Pad18)") (class "Default")
      (node (ref "U$2") (pin "18") (pinfunction "USBD-_18") (pintype "bidirectional"))
    )
    (net (code "99") (name "unconnected-(U1-STAT-Pad1)") (class "Default")
      (node (ref "U1") (pin "1") (pinfunction "STAT_1") (pintype "output"))
    )
    (net (code "100") (name "unconnected-(U3-ALT-Pad5)") (class "Default")
      (node (ref "U3") (pin "5") (pinfunction "ALT_5") (pintype "bidirectional"))
    )
    (net (code "101") (name "unconnected-(U4-BP-Pad4)") (class "Default")
      (node (ref "U4") (pin "4") (pinfunction "BP_4") (pintype "input"))
    )
  )
)
